# LM75_Breakout_wDrill.net
KiCad netlist of a schematic drawn in EAGLE
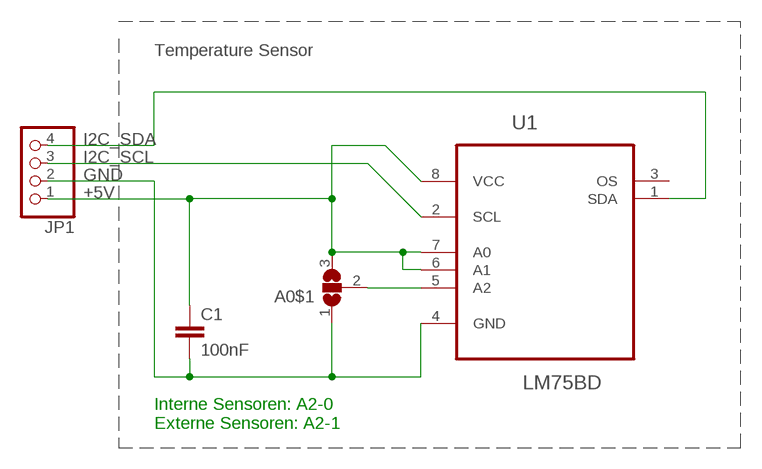
[diagram p0: schematic, sheet 1]

(export (version "E")
  (design (tool "Eeschema 10.0.6"))
  (components
    (comp (ref "A0$1")
      (value "SJ2W")
      (footprint "eagle-import:SJ_2")
      (libsource (lib "eagle-import") (part "SJ2W"))
    )
    (comp (ref "C1")
      (value "100nF")
      (footprint "eagle-import:C0805")
      (libsource (lib "eagle-import") (part "C-EUC0805"))
    )
    (comp (ref "JP1")
      (value "PINHD-1X4")
      (footprint "eagle-import:1X04")
      (libsource (lib "eagle-import") (part "PINHD-1X4"))
    )
    (comp (ref "U1")
      (value "LM75BD")
      (footprint "eagle-import:SOIC127P600X175-8N")
      (libsource (lib "eagle-import") (part "LM75BD"))
    )
  )
  (nets
    (net (code "1") (name "/+5V") (class "Default")
      (node (ref "A0$1") (pin "3") (pinfunction "3_3") (pintype "passive"))
      (node (ref "C1") (pin "1") (pinfunction "1_1") (pintype "passive"))
      (node (ref "JP1") (pin "1") (pinfunction "1_1") (pintype "passive"))
      (node (ref "U1") (pin "6") (pinfunction "A1_6") (pintype "input"))
      (node (ref "U1") (pin "7") (pinfunction "A0_7") (pintype "input"))
      (node (ref "U1") (pin "8") (pinfunction "VCC_8") (pintype "power_in"))
    )
    (net (code "2") (name "/GND") (class "Default")
      (node (ref "A0$1") (pin "1") (pinfunction "1_1") (pintype "passive"))
      (node (ref "C1") (pin "2") (pinfunction "2_2") (pintype "passive"))
      (node (ref "JP1") (pin "2") (pinfunction "2_2") (pintype "passive"))
      (node (ref "U1") (pin "4") (pinfunction "GND_4") (pintype "passive"))
    )
    (net (code "3") (name "/I2C_SCL") (class "Default")
      (node (ref "JP1") (pin "3") (pinfunction "3_3") (pintype "passive"))
      (node (ref "U1") (pin "2") (pinfunction "SCL_2") (pintype "input"))
    )
    (net (code "4") (name "/I2C_SDA") (class "Default")
      (node (ref "JP1") (pin "4") (pinfunction "4_4") (pintype "passive"))
      (node (ref "U1") (pin "1") (pinfunction "SDA_1") (pintype "bidirectional"))
    )
    (net (code "5") (name "Net-(U1-A2)") (class "Default")
      (node (ref "A0$1") (pin "2") (pinfunction "2_2") (pintype "passive"))
      (node (ref "U1") (pin "5") (pinfunction "A2_5") (pintype "input"))
    )
    (net (code "6") (name "unconnected-(U1-OS-Pad3)") (class "Default")
      (node (ref "U1") (pin "3") (pinfunction "OS_3") (pintype "output"))
    )
  )
)
